# schematic.net
KiCad netlist of a schematic drawn in EAGLE
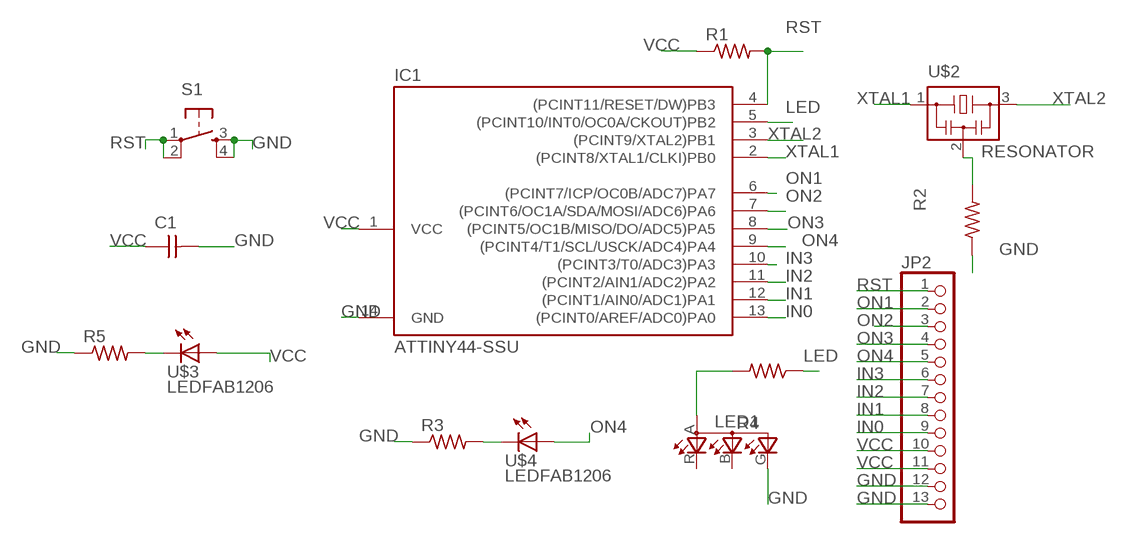
[diagram p0: schematic, sheet 1]

(export (version "E")
  (design (tool "Eeschema 10.0.6"))
  (components
    (comp (ref "C1")
      (value "CAP-UNPOLARIZEDFAB")
      (footprint "eagle-import:C1206FAB")
      (libsource (lib "eagle-import") (part "CAP-UNPOLARIZEDFAB"))
    )
    (comp (ref "IC1")
      (value "ATTINY44-SSU")
      (footprint "eagle-import:SOIC14")
      (libsource (lib "eagle-import") (part "ATTINY44-SSU"))
    )
    (comp (ref "JP2")
      (value "PINHD-1X131X13_SMT")
      (footprint "eagle-import:1X13_SMT")
      (libsource (lib "eagle-import") (part "PINHD-1X131X13_SMT"))
    )
    (comp (ref "LED1")
      (value "LEDRGBOLD")
      (footprint "eagle-import:P-LCC-4-3")
      (libsource (lib "eagle-import") (part "LEDRGBOLD"))
    )
    (comp (ref "R1")
      (value "RES-US1206FAB")
      (footprint "eagle-import:R1206FAB")
      (libsource (lib "eagle-import") (part "RES-US1206FAB"))
    )
    (comp (ref "R2")
      (value "RES-US1206FAB")
      (footprint "eagle-import:R1206FAB")
      (libsource (lib "eagle-import") (part "RES-US1206FAB"))
    )
    (comp (ref "R3")
      (value "RES-US1206FAB")
      (footprint "eagle-import:R1206FAB")
      (libsource (lib "eagle-import") (part "RES-US1206FAB"))
    )
    (comp (ref "R4")
      (value "RES-US1206FAB")
      (footprint "eagle-import:R1206FAB")
      (libsource (lib "eagle-import") (part "RES-US1206FAB"))
    )
    (comp (ref "R5")
      (value "RES-US1206FAB")
      (footprint "eagle-import:R1206FAB")
      (libsource (lib "eagle-import") (part "RES-US1206FAB"))
    )
    (comp (ref "S1")
      (value "6MM_SWITCH6MM_SWITCH")
      (footprint "eagle-import:6MM_SWITCH")
      (libsource (lib "eagle-import") (part "6MM_SWITCH6MM_SWITCH"))
    )
    (comp (ref "U$2")
      (value "RESONATOR")
      (footprint "eagle-import:EFOBM")
      (libsource (lib "eagle-import") (part "RESONATOR"))
    )
    (comp (ref "U$3")
      (value "LEDFAB1206")
      (footprint "eagle-import:LED1206FAB")
      (libsource (lib "eagle-import") (part "LEDFAB1206"))
    )
    (comp (ref "U$4")
      (value "LEDFAB1206")
      (footprint "eagle-import:LED1206FAB")
      (libsource (lib "eagle-import") (part "LEDFAB1206"))
    )
  )
  (nets
    (net (code "1") (name "/GND") (class "Default")
      (node (ref "C1") (pin "2") (pinfunction "2_2") (pintype "passive"))
      (node (ref "IC1") (pin "14") (pinfunction "GND_14") (pintype "power_in"))
      (node (ref "JP2") (pin "12") (pinfunction "12_12") (pintype "passive"))
      (node (ref "JP2") (pin "13") (pinfunction "13_13") (pintype "passive"))
      (node (ref "LED1") (pin "G") (pinfunction "CGREEN_G") (pintype "passive"))
      (node (ref "R2") (pin "1") (pinfunction "1_1") (pintype "passive"))
      (node (ref "R3") (pin "1") (pinfunction "1_1") (pintype "passive"))
      (node (ref "R5") (pin "1") (pinfunction "1_1") (pintype "passive"))
      (node (ref "S1") (pin "3") (pinfunction "S_3") (pintype "passive"))
      (node (ref "S1") (pin "4") (pinfunction "S1_4") (pintype "passive"))
    )
    (net (code "2") (name "/IN0") (class "Default")
      (node (ref "IC1") (pin "13") (pinfunction "(PCINT0/AREF/ADC0)PA0_13") (pintype "bidirectional"))
      (node (ref "JP2") (pin "9") (pinfunction "9_9") (pintype "passive"))
    )
    (net (code "3") (name "/IN1") (class "Default")
      (node (ref "IC1") (pin "12") (pinfunction "(PCINT1/AIN0/ADC1)PA1_12") (pintype "bidirectional"))
      (node (ref "JP2") (pin "8") (pinfunction "8_8") (pintype "passive"))
    )
    (net (code "4") (name "/IN2") (class "Default")
      (node (ref "IC1") (pin "11") (pinfunction "(PCINT2/AIN1/ADC2)PA2_11") (pintype "bidirectional"))
      (node (ref "JP2") (pin "7") (pinfunction "7_7") (pintype "passive"))
    )
    (net (code "5") (name "/IN3") (class "Default")
      (node (ref "IC1") (pin "10") (pinfunction "(PCINT3/T0/ADC3)PA3_10") (pintype "bidirectional"))
      (node (ref "JP2") (pin "6") (pinfunction "6_6") (pintype "passive"))
    )
    (net (code "6") (name "/LED") (class "Default")
      (node (ref "IC1") (pin "5") (pinfunction "(PCINT10/INT0/OC0A/CKOUT)PB2_5") (pintype "bidirectional"))
      (node (ref "R4") (pin "1") (pinfunction "1_1") (pintype "passive"))
    )
    (net (code "7") (name "/ON1") (class "Default")
      (node (ref "IC1") (pin "6") (pinfunction "(PCINT7/ICP/OC0B/ADC7)PA7_6") (pintype "bidirectional"))
      (node (ref "JP2") (pin "2") (pinfunction "2_2") (pintype "passive"))
    )
    (net (code "8") (name "/ON2") (class "Default")
      (node (ref "IC1") (pin "7") (pinfunction "(PCINT6/OC1A/SDA/MOSI/ADC6)PA6_7") (pintype "bidirectional"))
      (node (ref "JP2") (pin "3") (pinfunction "3_3") (pintype "passive"))
    )
    (net (code "9") (name "/ON3") (class "Default")
      (node (ref "IC1") (pin "8") (pinfunction "(PCINT5/OC1B/MISO/DO/ADC5)PA5_8") (pintype "bidirectional"))
      (node (ref "JP2") (pin "4") (pinfunction "4_4") (pintype "passive"))
    )
    (net (code "10") (name "/ON4") (class "Default")
      (node (ref "IC1") (pin "9") (pinfunction "(PCINT4/T1/SCL/USCK/ADC4)PA4_9") (pintype "bidirectional"))
      (node (ref "JP2") (pin "5") (pinfunction "5_5") (pintype "passive"))
      (node (ref "U$4") (pin "1") (pinfunction "A_1") (pintype "passive"))
    )
    (net (code "11") (name "/RST") (class "Default")
      (node (ref "IC1") (pin "4") (pinfunction "(PCINT11/RESET/DW)PB3_4") (pintype "bidirectional"))
      (node (ref "JP2") (pin "1") (pinfunction "1_1") (pintype "passive"))
      (node (ref "R1") (pin "2") (pinfunction "2_2") (pintype "passive"))
      (node (ref "S1") (pin "1") (pinfunction "P_1") (pintype "passive"))
      (node (ref "S1") (pin "2") (pinfunction "P1_2") (pintype "passive"))
    )
    (net (code "12") (name "/VCC") (class "Default")
      (node (ref "C1") (pin "1") (pinfunction "1_1") (pintype "passive"))
      (node (ref "IC1") (pin "1") (pinfunction "VCC_1") (pintype "power_in"))
      (node (ref "JP2") (pin "10") (pinfunction "10_10") (pintype "passive"))
      (node (ref "JP2") (pin "11") (pinfunction "11_11") (pintype "passive"))
      (node (ref "R1") (pin "1") (pinfunction "1_1") (pintype "passive"))
      (node (ref "U$3") (pin "1") (pinfunction "A_1") (pintype "passive"))
    )
    (net (code "13") (name "/XTAL1") (class "Default")
      (node (ref "IC1") (pin "2") (pinfunction "(PCINT8/XTAL1/CLKI)PB0_2") (pintype "bidirectional"))
      (node (ref "U$2") (pin "1") (pinfunction "1_1") (pintype "passive"))
    )
    (net (code "14") (name "/XTAL2") (class "Default")
      (node (ref "IC1") (pin "3") (pinfunction "(PCINT9/XTAL2)PB1_3") (pintype "bidirectional"))
      (node (ref "U$2") (pin "3") (pinfunction "3_3") (pintype "passive"))
    )
    (net (code "15") (name "Net-(LED1-A2)") (class "Default")
      (node (ref "LED1") (pin "A") (pinfunction "A2_A") (pintype "passive"))
      (node (ref "R4") (pin "2") (pinfunction "2_2") (pintype "passive"))
    )
    (net (code "16") (name "Net-(R2-Pad2)") (class "Default")
      (node (ref "R2") (pin "2") (pinfunction "2_2") (pintype "passive"))
      (node (ref "U$2") (pin "2") (pinfunction "2_2") (pintype "passive"))
    )
    (net (code "17") (name "Net-(U$3-C)") (class "Default")
      (node (ref "R5") (pin "2") (pinfunction "2_2") (pintype "passive"))
      (node (ref "U$3") (pin "2") (pinfunction "C_2") (pintype "passive"))
    )
    (net (code "18") (name "Net-(U$4-C)") (class "Default")
      (node (ref "R3") (pin "2") (pinfunction "2_2") (pintype "passive"))
      (node (ref "U$4") (pin "2") (pinfunction "C_2") (pintype "passive"))
    )
    (net (code "19") (name "unconnected-(LED1-CBLUE-PadB)") (class "Default")
      (node (ref "LED1") (pin "B") (pinfunction "CBLUE_B") (pintype "passive"))
    )
    (net (code "20") (name "unconnected-(LED1-CRED-PadR)") (class "Default")
      (node (ref "LED1") (pin "R") (pinfunction "CRED_R") (pintype "passive"))
    )
  )
)
